# blinkm_mk2j1.net
KiCad netlist of a schematic drawn in EAGLE
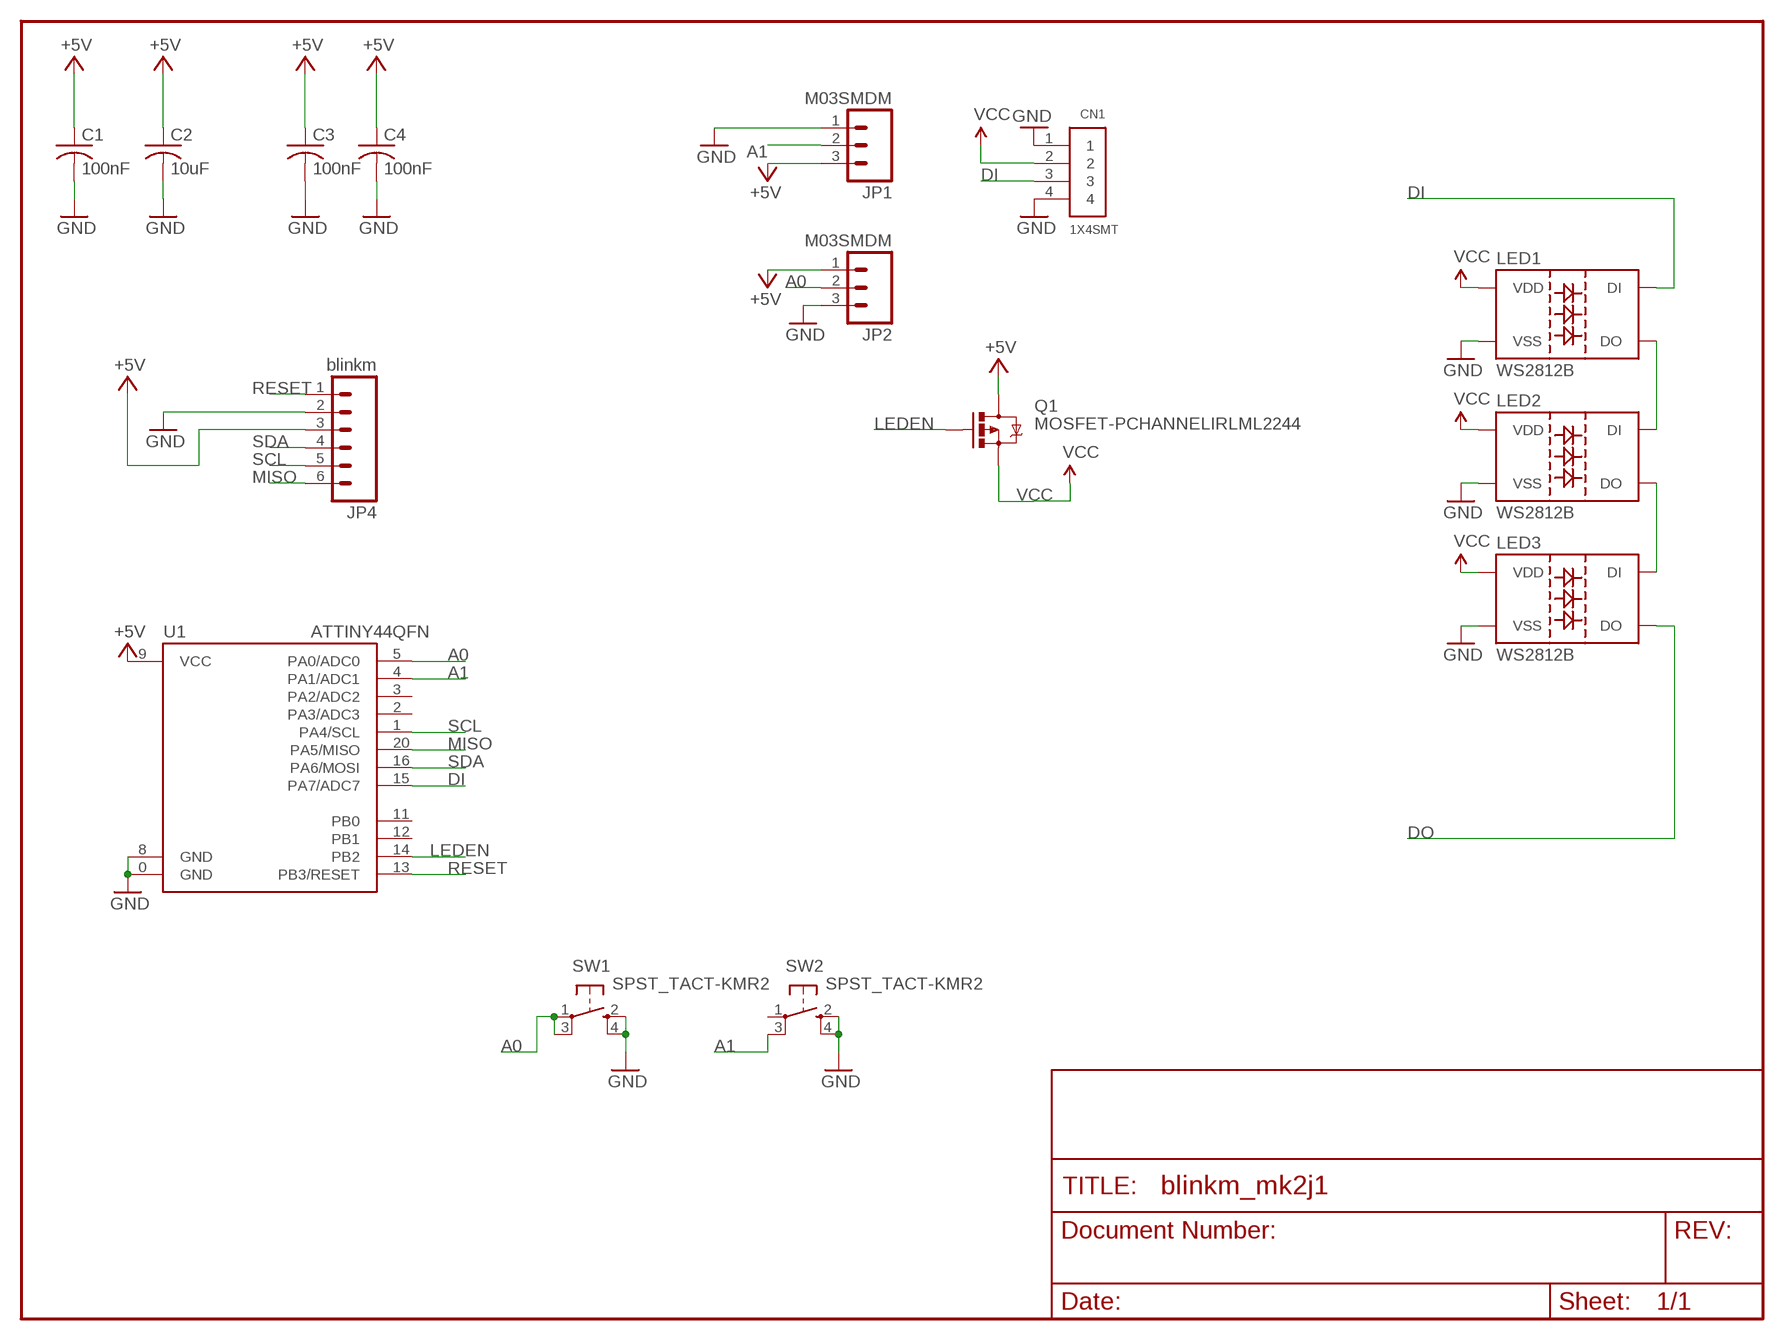
[diagram p0: schematic, sheet 1]

(export (version "E")
  (design (tool "Eeschema 10.0.6"))
  (components
    (comp (ref "C1")
      (value "100nF")
      (footprint "eagle-import:C0603")
      (libsource (lib "eagle-import") (part "C-USC0603"))
    )
    (comp (ref "C2")
      (value "10uF")
      (footprint "eagle-import:C0603")
      (libsource (lib "eagle-import") (part "C-USC0603"))
    )
    (comp (ref "C3")
      (value "100nF")
      (footprint "eagle-import:C0603")
      (libsource (lib "eagle-import") (part "C-USC0603"))
    )
    (comp (ref "C4")
      (value "100nF")
      (footprint "eagle-import:C0603")
      (libsource (lib "eagle-import") (part "C-USC0603"))
    )
    (comp (ref "CN1")
      (value "1X4SMT")
      (footprint "eagle-import:1X4-SMT")
      (libsource (lib "eagle-import") (part "1X4SMT"))
    )
    (comp (ref "JP1")
      (value "M03SMDM")
      (footprint "eagle-import:1X03-SMD-MINIMAL")
      (libsource (lib "eagle-import") (part "M03SMDM"))
    )
    (comp (ref "JP2")
      (value "M03SMDM")
      (footprint "eagle-import:1X03-SMD-MINIMAL")
      (libsource (lib "eagle-import") (part "M03SMDM"))
    )
    (comp (ref "JP4")
      (value "blinkm")
      (footprint "eagle-import:1X06_LOCK")
      (libsource (lib "eagle-import") (part "M06LOCK"))
    )
    (comp (ref "LED1")
      (value "WS2812B")
      (footprint "eagle-import:WS2812B")
      (libsource (lib "eagle-import") (part "WS2812B"))
    )
    (comp (ref "LED2")
      (value "WS2812B")
      (footprint "eagle-import:WS2812B")
      (libsource (lib "eagle-import") (part "WS2812B"))
    )
    (comp (ref "LED3")
      (value "WS2812B")
      (footprint "eagle-import:WS2812B")
      (libsource (lib "eagle-import") (part "WS2812B"))
    )
    (comp (ref "Q1")
      (value "MOSFET-PCHANNELIRLML2244")
      (footprint "eagle-import:SOT23-3")
      (libsource (lib "eagle-import") (part "MOSFET-PCHANNELIRLML2244"))
    )
    (comp (ref "SW1")
      (value "SPST_TACT-KMR2")
      (footprint "eagle-import:KMR2")
      (libsource (lib "eagle-import") (part "SPST_TACT-KMR2"))
    )
    (comp (ref "SW2")
      (value "SPST_TACT-KMR2")
      (footprint "eagle-import:KMR2")
      (libsource (lib "eagle-import") (part "SPST_TACT-KMR2"))
    )
    (comp (ref "U1")
      (value "ATTINY44QFN")
      (footprint "eagle-import:QFN20")
      (libsource (lib "eagle-import") (part "ATTINY24QFN"))
    )
  )
  (nets
    (net (code "1") (name "+5V") (class "Default")
      (node (ref "C1") (pin "1") (pinfunction "1_1") (pintype "passive"))
      (node (ref "C2") (pin "1") (pinfunction "1_1") (pintype "passive"))
      (node (ref "C3") (pin "1") (pinfunction "1_1") (pintype "passive"))
      (node (ref "C4") (pin "1") (pinfunction "1_1") (pintype "passive"))
      (node (ref "JP1") (pin "3") (pinfunction "3_3") (pintype "passive"))
      (node (ref "JP2") (pin "1") (pinfunction "1_1") (pintype "passive"))
      (node (ref "JP4") (pin "3") (pinfunction "3_3") (pintype "passive"))
      (node (ref "Q1") (pin "3") (pinfunction "D_3") (pintype "passive"))
      (node (ref "U1") (pin "9") (pinfunction "VCC_9") (pintype "bidirectional"))
    )
    (net (code "2") (name "/A0") (class "Default")
      (node (ref "JP2") (pin "2") (pinfunction "2_2") (pintype "passive"))
      (node (ref "SW1") (pin "1") (pinfunction "P_1") (pintype "passive"))
      (node (ref "SW1") (pin "3") (pinfunction "P1_3") (pintype "passive"))
      (node (ref "U1") (pin "5") (pinfunction "PA0/ADC0_5") (pintype "bidirectional"))
    )
    (net (code "3") (name "/A1") (class "Default")
      (node (ref "JP1") (pin "2") (pinfunction "2_2") (pintype "passive"))
      (node (ref "SW2") (pin "3") (pinfunction "P1_3") (pintype "passive"))
      (node (ref "U1") (pin "4") (pinfunction "PA1/ADC1_4") (pintype "bidirectional"))
    )
    (net (code "4") (name "/DI") (class "Default")
      (node (ref "CN1") (pin "3") (pinfunction "3_3") (pintype "bidirectional"))
      (node (ref "LED1") (pin "4") (pinfunction "DI_4") (pintype "bidirectional"))
      (node (ref "U1") (pin "15") (pinfunction "PA7/ADC7_15") (pintype "bidirectional"))
    )
    (net (code "5") (name "/DO") (class "Default")
      (node (ref "LED3") (pin "2") (pinfunction "DO_2") (pintype "bidirectional"))
    )
    (net (code "6") (name "/LEDEN") (class "Default")
      (node (ref "Q1") (pin "1") (pinfunction "G_1") (pintype "passive"))
      (node (ref "U1") (pin "14") (pinfunction "PB2_14") (pintype "bidirectional"))
    )
    (net (code "7") (name "/MISO") (class "Default")
      (node (ref "JP4") (pin "6") (pinfunction "6_6") (pintype "passive"))
      (node (ref "U1") (pin "20") (pinfunction "PA5/MISO_20") (pintype "bidirectional"))
    )
    (net (code "8") (name "/RESET") (class "Default")
      (node (ref "JP4") (pin "1") (pinfunction "1_1") (pintype "passive"))
      (node (ref "U1") (pin "13") (pinfunction "PB3/RESET_13") (pintype "bidirectional"))
    )
    (net (code "9") (name "/SCL") (class "Default")
      (node (ref "JP4") (pin "5") (pinfunction "5_5") (pintype "passive"))
      (node (ref "U1") (pin "1") (pinfunction "PA4/SCL_1") (pintype "bidirectional"))
    )
    (net (code "10") (name "/SDA") (class "Default")
      (node (ref "JP4") (pin "4") (pinfunction "4_4") (pintype "passive"))
      (node (ref "U1") (pin "16") (pinfunction "PA6/MOSI_16") (pintype "bidirectional"))
    )
    (net (code "11") (name "GND") (class "Default")
      (node (ref "C1") (pin "2") (pinfunction "2_2") (pintype "passive"))
      (node (ref "C2") (pin "2") (pinfunction "2_2") (pintype "passive"))
      (node (ref "C3") (pin "2") (pinfunction "2_2") (pintype "passive"))
      (node (ref "C4") (pin "2") (pinfunction "2_2") (pintype "passive"))
      (node (ref "CN1") (pin "1") (pinfunction "1_1") (pintype "bidirectional"))
      (node (ref "CN1") (pin "4") (pinfunction "4_4") (pintype "bidirectional"))
      (node (ref "JP1") (pin "1") (pinfunction "1_1") (pintype "passive"))
      (node (ref "JP2") (pin "3") (pinfunction "3_3") (pintype "passive"))
      (node (ref "JP4") (pin "2") (pinfunction "2_2") (pintype "passive"))
      (node (ref "LED1") (pin "3") (pinfunction "VSS_3") (pintype "bidirectional"))
      (node (ref "LED2") (pin "3") (pinfunction "VSS_3") (pintype "bidirectional"))
      (node (ref "LED3") (pin "3") (pinfunction "VSS_3") (pintype "bidirectional"))
      (node (ref "SW1") (pin "2") (pinfunction "S_2") (pintype "passive"))
      (node (ref "SW1") (pin "4") (pinfunction "S1_4") (pintype "passive"))
      (node (ref "SW2") (pin "2") (pinfunction "S_2") (pintype "passive"))
      (node (ref "SW2") (pin "4") (pinfunction "S1_4") (pintype "passive"))
      (node (ref "U1") (pin "0") (pinfunction "GND_0") (pintype "bidirectional"))
      (node (ref "U1") (pin "8") (pinfunction "GND_8") (pintype "bidirectional"))
    )
    (net (code "12") (name "Net-(LED1-DO)") (class "Default")
      (node (ref "LED1") (pin "2") (pinfunction "DO_2") (pintype "bidirectional"))
      (node (ref "LED2") (pin "4") (pinfunction "DI_4") (pintype "bidirectional"))
    )
    (net (code "13") (name "Net-(LED2-DO)") (class "Default")
      (node (ref "LED2") (pin "2") (pinfunction "DO_2") (pintype "bidirectional"))
      (node (ref "LED3") (pin "4") (pinfunction "DI_4") (pintype "bidirectional"))
    )
    (net (code "14") (name "VCC") (class "Default")
      (node (ref "CN1") (pin "2") (pinfunction "2_2") (pintype "bidirectional"))
      (node (ref "LED1") (pin "1") (pinfunction "VDD_1") (pintype "bidirectional"))
      (node (ref "LED2") (pin "1") (pinfunction "VDD_1") (pintype "bidirectional"))
      (node (ref "LED3") (pin "1") (pinfunction "VDD_1") (pintype "bidirectional"))
      (node (ref "Q1") (pin "2") (pinfunction "S_2") (pintype "passive"))
    )
    (net (code "15") (name "unconnected-(SW2-P-Pad1)") (class "Default")
      (node (ref "SW2") (pin "1") (pinfunction "P_1") (pintype "passive"))
    )
    (net (code "16") (name "unconnected-(U1-PA2{slash}ADC2-Pad3)") (class "Default")
      (node (ref "U1") (pin "3") (pinfunction "PA2/ADC2_3") (pintype "bidirectional"))
    )
    (net (code "17") (name "unconnected-(U1-PA3{slash}ADC3-Pad2)") (class "Default")
      (node (ref "U1") (pin "2") (pinfunction "PA3/ADC3_2") (pintype "bidirectional"))
    )
    (net (code "18") (name "unconnected-(U1-PB0-Pad11)") (class "Default")
      (node (ref "U1") (pin "11") (pinfunction "PB0_11") (pintype "bidirectional"))
    )
    (net (code "19") (name "unconnected-(U1-PB1-Pad12)") (class "Default")
      (node (ref "U1") (pin "12") (pinfunction "PB1_12") (pintype "bidirectional"))
    )
  )
)
